# Thing_Plus_Qwiic_Shield.net
KiCad netlist of a schematic drawn in EAGLE
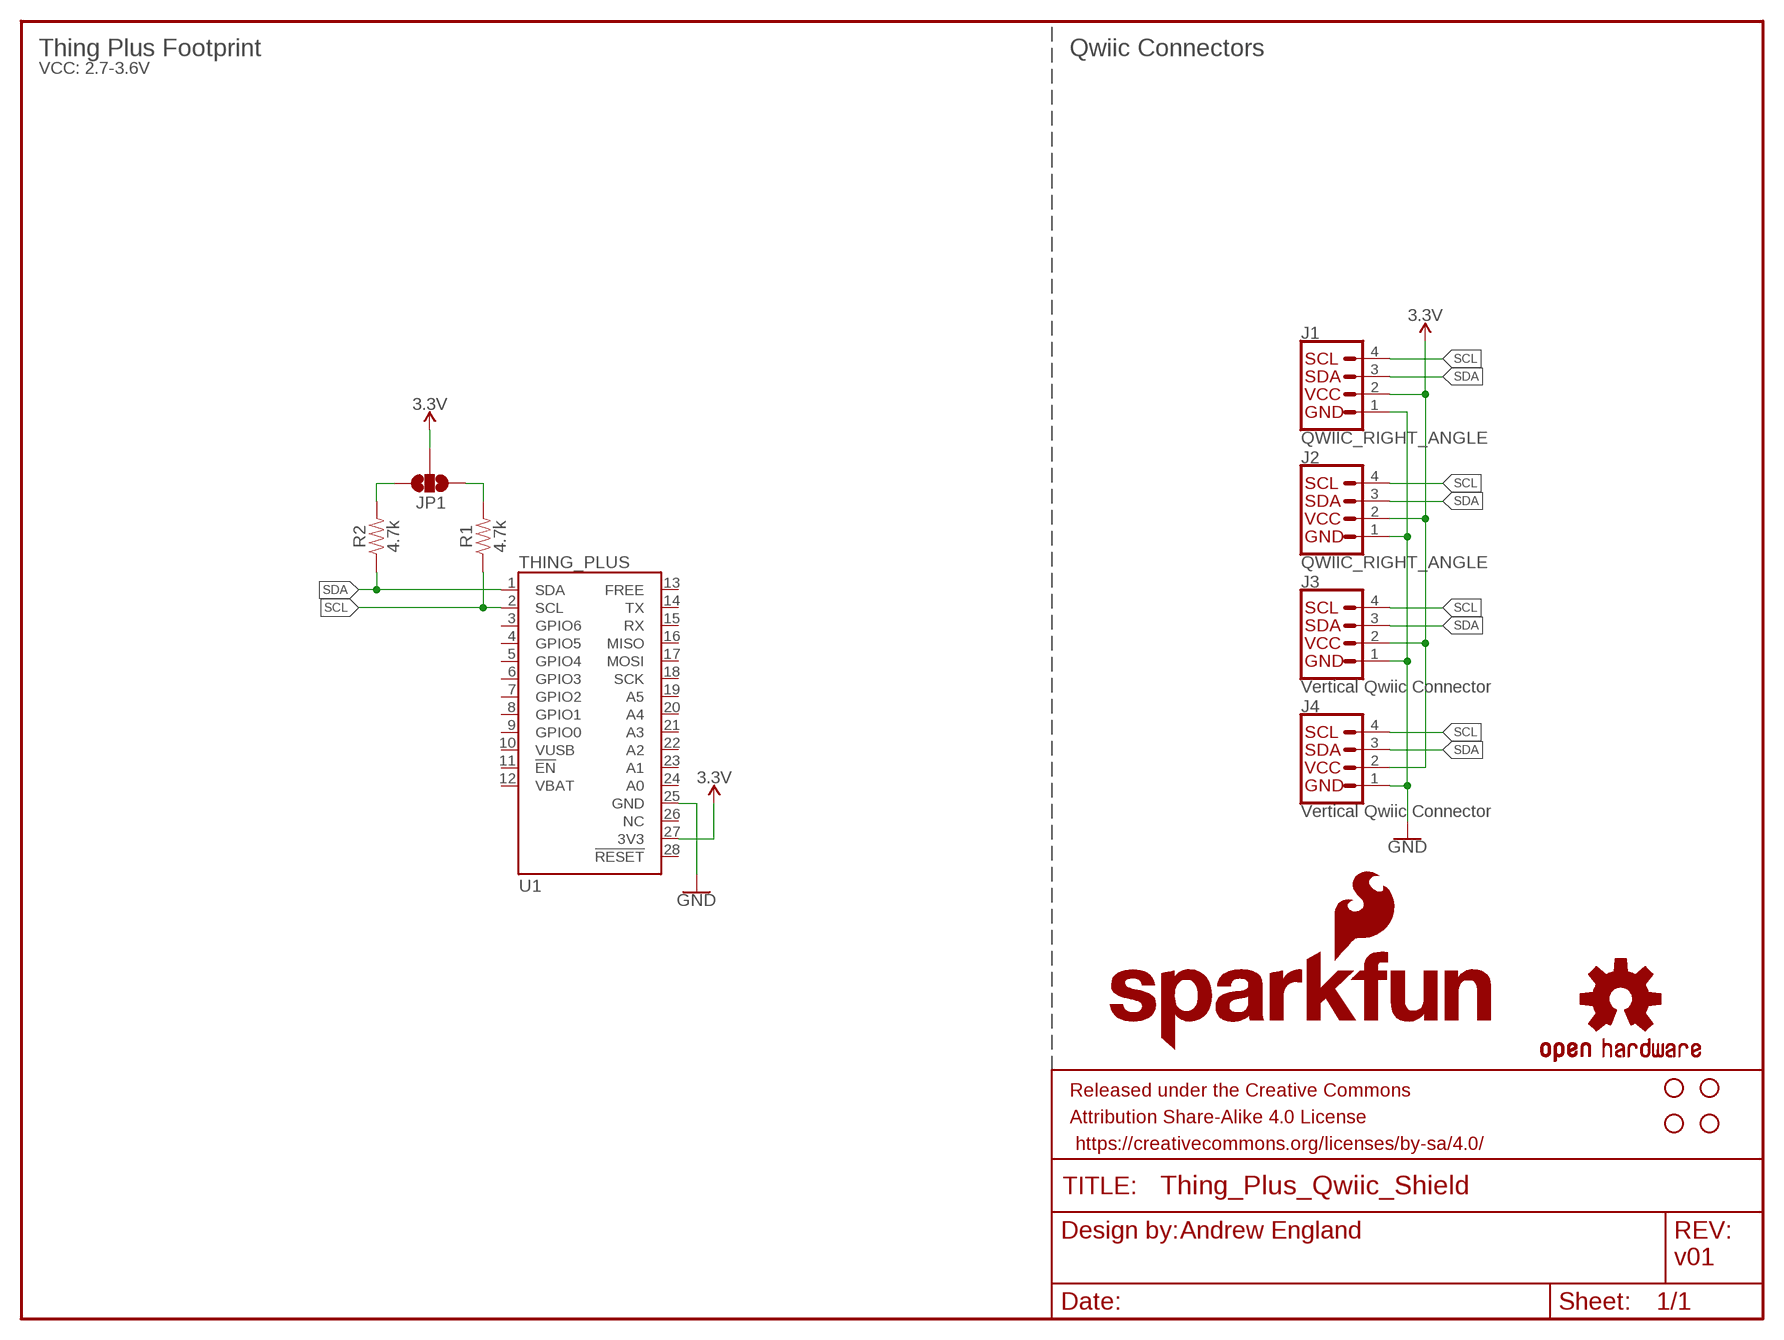
[diagram p0: schematic, sheet 1]

(export (version "E")
  (design (tool "Eeschema 10.0.6"))
  (components
    (comp (ref "FRAME1")
      (value "FRAME-LETTER")
      (footprint "eagle-import:CREATIVE_COMMONS")
      (libsource (lib "eagle-import") (part "FRAME-LETTER"))
    )
    (comp (ref "H1")
      (value "STAND-OFF")
      (footprint "eagle-import:STAND-OFF")
      (libsource (lib "eagle-import") (part "STAND-OFF"))
    )
    (comp (ref "H2")
      (value "STAND-OFF")
      (footprint "eagle-import:STAND-OFF")
      (libsource (lib "eagle-import") (part "STAND-OFF"))
    )
    (comp (ref "H3")
      (value "STAND-OFF")
      (footprint "eagle-import:STAND-OFF")
      (libsource (lib "eagle-import") (part "STAND-OFF"))
    )
    (comp (ref "H4")
      (value "STAND-OFF")
      (footprint "eagle-import:STAND-OFF")
      (libsource (lib "eagle-import") (part "STAND-OFF"))
    )
    (comp (ref "J1")
      (value "QWIIC_RIGHT_ANGLE")
      (footprint "eagle-import:JST04_1MM_RA")
      (libsource (lib "eagle-import") (part "QWIIC_CONNECTORJS-1MM"))
    )
    (comp (ref "J2")
      (value "QWIIC_RIGHT_ANGLE")
      (footprint "eagle-import:JST04_1MM_RA")
      (libsource (lib "eagle-import") (part "QWIIC_CONNECTORJS-1MM"))
    )
    (comp (ref "J3")
      (value "Vertical Qwiic Connector")
      (footprint "eagle-import:JST04_1MM_VERT")
      (libsource (lib "eagle-import") (part "QWIIC_CONNECTOR"))
    )
    (comp (ref "J4")
      (value "Vertical Qwiic Connector")
      (footprint "eagle-import:JST04_1MM_VERT")
      (libsource (lib "eagle-import") (part "QWIIC_CONNECTOR"))
    )
    (comp (ref "JP1")
      (value "JUMPER-SMT_3_NO_NO-SILK")
      (footprint "eagle-import:SMT-JUMPER_3_NO_NO-SILK")
      (libsource (lib "eagle-import") (part "JUMPER-SMT_3_NO_NO-SILK"))
    )
    (comp (ref "LOGO1")
      (value "SFE_LOGO_NAME_FLAME.1_INCH")
      (footprint "eagle-import:SFE_LOGO_NAME_FLAME_.1")
      (libsource (lib "eagle-import") (part "SFE_LOGO_NAME_FLAME.1_INCH"))
    )
    (comp (ref "LOGO2")
      (value "SFE_LOGO_NAME_FLAME.2_INCH")
      (footprint "eagle-import:SFE_LOGO_NAME_FLAME_.2")
      (libsource (lib "eagle-import") (part "SFE_LOGO_NAME_FLAME.2_INCH"))
    )
    (comp (ref "LOGO3")
      (value "OSHW-LOGOS")
      (footprint "eagle-import:OSHW-LOGO-S")
      (libsource (lib "eagle-import") (part "OSHW-LOGOS"))
    )
    (comp (ref "R1")
      (value "4.7k")
      (footprint "eagle-import:0603")
      (libsource (lib "eagle-import") (part "4.7KOHM-0603-1/10W-1%"))
    )
    (comp (ref "R2")
      (value "4.7k")
      (footprint "eagle-import:0603")
      (libsource (lib "eagle-import") (part "4.7KOHM-0603-1/10W-1%"))
    )
    (comp (ref "U1")
      (value "THING_PLUS")
      (footprint "eagle-import:THING_PLUS")
      (libsource (lib "eagle-import") (part "THING_PLUS"))
    )
  )
  (nets
    (net (code "1") (name "3.3V") (class "Default")
      (node (ref "J1") (pin "2") (pinfunction "2_2") (pintype "power_in"))
      (node (ref "J2") (pin "2") (pinfunction "2_2") (pintype "power_in"))
      (node (ref "J3") (pin "2") (pinfunction "2_2") (pintype "power_in"))
      (node (ref "J4") (pin "2") (pinfunction "2_2") (pintype "power_in"))
      (node (ref "JP1") (pin "2") (pinfunction "2_2") (pintype "passive"))
      (node (ref "U1") (pin "27") (pinfunction "3V3_27") (pintype "bidirectional"))
    )
    (net (code "2") (name "GND") (class "Default")
      (node (ref "J1") (pin "1") (pinfunction "1_1") (pintype "power_in"))
      (node (ref "J2") (pin "1") (pinfunction "1_1") (pintype "power_in"))
      (node (ref "J3") (pin "1") (pinfunction "1_1") (pintype "power_in"))
      (node (ref "J4") (pin "1") (pinfunction "1_1") (pintype "power_in"))
      (node (ref "U1") (pin "25") (pinfunction "GND_25") (pintype "bidirectional"))
    )
    (net (code "3") (name "Net-(JP1-Pad1)") (class "Default")
      (node (ref "JP1") (pin "1") (pinfunction "1_1") (pintype "passive"))
      (node (ref "R1") (pin "2") (pinfunction "2_2") (pintype "passive"))
    )
    (net (code "4") (name "Net-(JP1-Pad3)") (class "Default")
      (node (ref "JP1") (pin "3") (pinfunction "3_3") (pintype "passive"))
      (node (ref "R2") (pin "2") (pinfunction "2_2") (pintype "passive"))
    )
    (net (code "5") (name "SCL") (class "Default")
      (node (ref "J1") (pin "4") (pinfunction "4_4") (pintype "passive"))
      (node (ref "J2") (pin "4") (pinfunction "4_4") (pintype "passive"))
      (node (ref "J3") (pin "4") (pinfunction "4_4") (pintype "passive"))
      (node (ref "J4") (pin "4") (pinfunction "4_4") (pintype "passive"))
      (node (ref "R1") (pin "1") (pinfunction "1_1") (pintype "passive"))
      (node (ref "U1") (pin "2") (pinfunction "SCL_2") (pintype "bidirectional"))
    )
    (net (code "6") (name "SDA") (class "Default")
      (node (ref "J1") (pin "3") (pinfunction "3_3") (pintype "passive"))
      (node (ref "J2") (pin "3") (pinfunction "3_3") (pintype "passive"))
      (node (ref "J3") (pin "3") (pinfunction "3_3") (pintype "passive"))
      (node (ref "J4") (pin "3") (pinfunction "3_3") (pintype "passive"))
      (node (ref "R2") (pin "1") (pinfunction "1_1") (pintype "passive"))
      (node (ref "U1") (pin "1") (pinfunction "SDA_1") (pintype "bidirectional"))
    )
    (net (code "7") (name "unconnected-(U1-A0-Pad24)") (class "Default")
      (node (ref "U1") (pin "24") (pinfunction "A0_24") (pintype "bidirectional"))
    )
    (net (code "8") (name "unconnected-(U1-A1-Pad23)") (class "Default")
      (node (ref "U1") (pin "23") (pinfunction "A1_23") (pintype "bidirectional"))
    )
    (net (code "9") (name "unconnected-(U1-A2-Pad22)") (class "Default")
      (node (ref "U1") (pin "22") (pinfunction "A2_22") (pintype "bidirectional"))
    )
    (net (code "10") (name "unconnected-(U1-A3-Pad21)") (class "Default")
      (node (ref "U1") (pin "21") (pinfunction "A3_21") (pintype "bidirectional"))
    )
    (net (code "11") (name "unconnected-(U1-A4-Pad20)") (class "Default")
      (node (ref "U1") (pin "20") (pinfunction "A4_20") (pintype "bidirectional"))
    )
    (net (code "12") (name "unconnected-(U1-A5-Pad19)") (class "Default")
      (node (ref "U1") (pin "19") (pinfunction "A5_19") (pintype "bidirectional"))
    )
    (net (code "13") (name "unconnected-(U1-FREE-Pad13)") (class "Default")
      (node (ref "U1") (pin "13") (pinfunction "FREE_13") (pintype "bidirectional"))
    )
    (net (code "14") (name "unconnected-(U1-GPIO0-Pad9)") (class "Default")
      (node (ref "U1") (pin "9") (pinfunction "GPIO0_9") (pintype "bidirectional"))
    )
    (net (code "15") (name "unconnected-(U1-GPIO1-Pad8)") (class "Default")
      (node (ref "U1") (pin "8") (pinfunction "GPIO1_8") (pintype "bidirectional"))
    )
    (net (code "16") (name "unconnected-(U1-GPIO2-Pad7)") (class "Default")
      (node (ref "U1") (pin "7") (pinfunction "GPIO2_7") (pintype "bidirectional"))
    )
    (net (code "17") (name "unconnected-(U1-GPIO3-Pad6)") (class "Default")
      (node (ref "U1") (pin "6") (pinfunction "GPIO3_6") (pintype "bidirectional"))
    )
    (net (code "18") (name "unconnected-(U1-GPIO4-Pad5)") (class "Default")
      (node (ref "U1") (pin "5") (pinfunction "GPIO4_5") (pintype "bidirectional"))
    )
    (net (code "19") (name "unconnected-(U1-GPIO5-Pad4)") (class "Default")
      (node (ref "U1") (pin "4") (pinfunction "GPIO5_4") (pintype "bidirectional"))
    )
    (net (code "20") (name "unconnected-(U1-GPIO6-Pad3)") (class "Default")
      (node (ref "U1") (pin "3") (pinfunction "GPIO6_3") (pintype "bidirectional"))
    )
    (net (code "21") (name "unconnected-(U1-MISO-Pad16)") (class "Default")
      (node (ref "U1") (pin "16") (pinfunction "MISO_16") (pintype "bidirectional"))
    )
    (net (code "22") (name "unconnected-(U1-MOSI-Pad17)") (class "Default")
      (node (ref "U1") (pin "17") (pinfunction "MOSI_17") (pintype "bidirectional"))
    )
    (net (code "23") (name "unconnected-(U1-NC-Pad26)") (class "Default")
      (node (ref "U1") (pin "26") (pinfunction "NC_26") (pintype "bidirectional"))
    )
    (net (code "24") (name "unconnected-(U1-RX-Pad15)") (class "Default")
      (node (ref "U1") (pin "15") (pinfunction "RX_15") (pintype "bidirectional"))
    )
    (net (code "25") (name "unconnected-(U1-SCK-Pad18)") (class "Default")
      (node (ref "U1") (pin "18") (pinfunction "SCK_18") (pintype "bidirectional"))
    )
    (net (code "26") (name "unconnected-(U1-TX-Pad14)") (class "Default")
      (node (ref "U1") (pin "14") (pinfunction "TX_14") (pintype "bidirectional"))
    )
    (net (code "27") (name "unconnected-(U1-VBAT-Pad12)") (class "Default")
      (node (ref "U1") (pin "12") (pinfunction "VBAT_12") (pintype "bidirectional"))
    )
    (net (code "28") (name "unconnected-(U1-VUSB-Pad10)") (class "Default")
      (node (ref "U1") (pin "10") (pinfunction "VUSB_10") (pintype "bidirectional"))
    )
    (net (code "29") (name "unconnected-(U1-~{EN}-Pad11)") (class "Default")
      (node (ref "U1") (pin "11") (pinfunction "~{EN}_11") (pintype "bidirectional"))
    )
    (net (code "30") (name "unconnected-(U1-~{RESET}-Pad28)") (class "Default")
      (node (ref "U1") (pin "28") (pinfunction "~{RESET}_28") (pintype "bidirectional"))
    )
  )
)
